# Precision_Arduino_Charlieplex.net
KiCad netlist of a schematic drawn in EAGLE
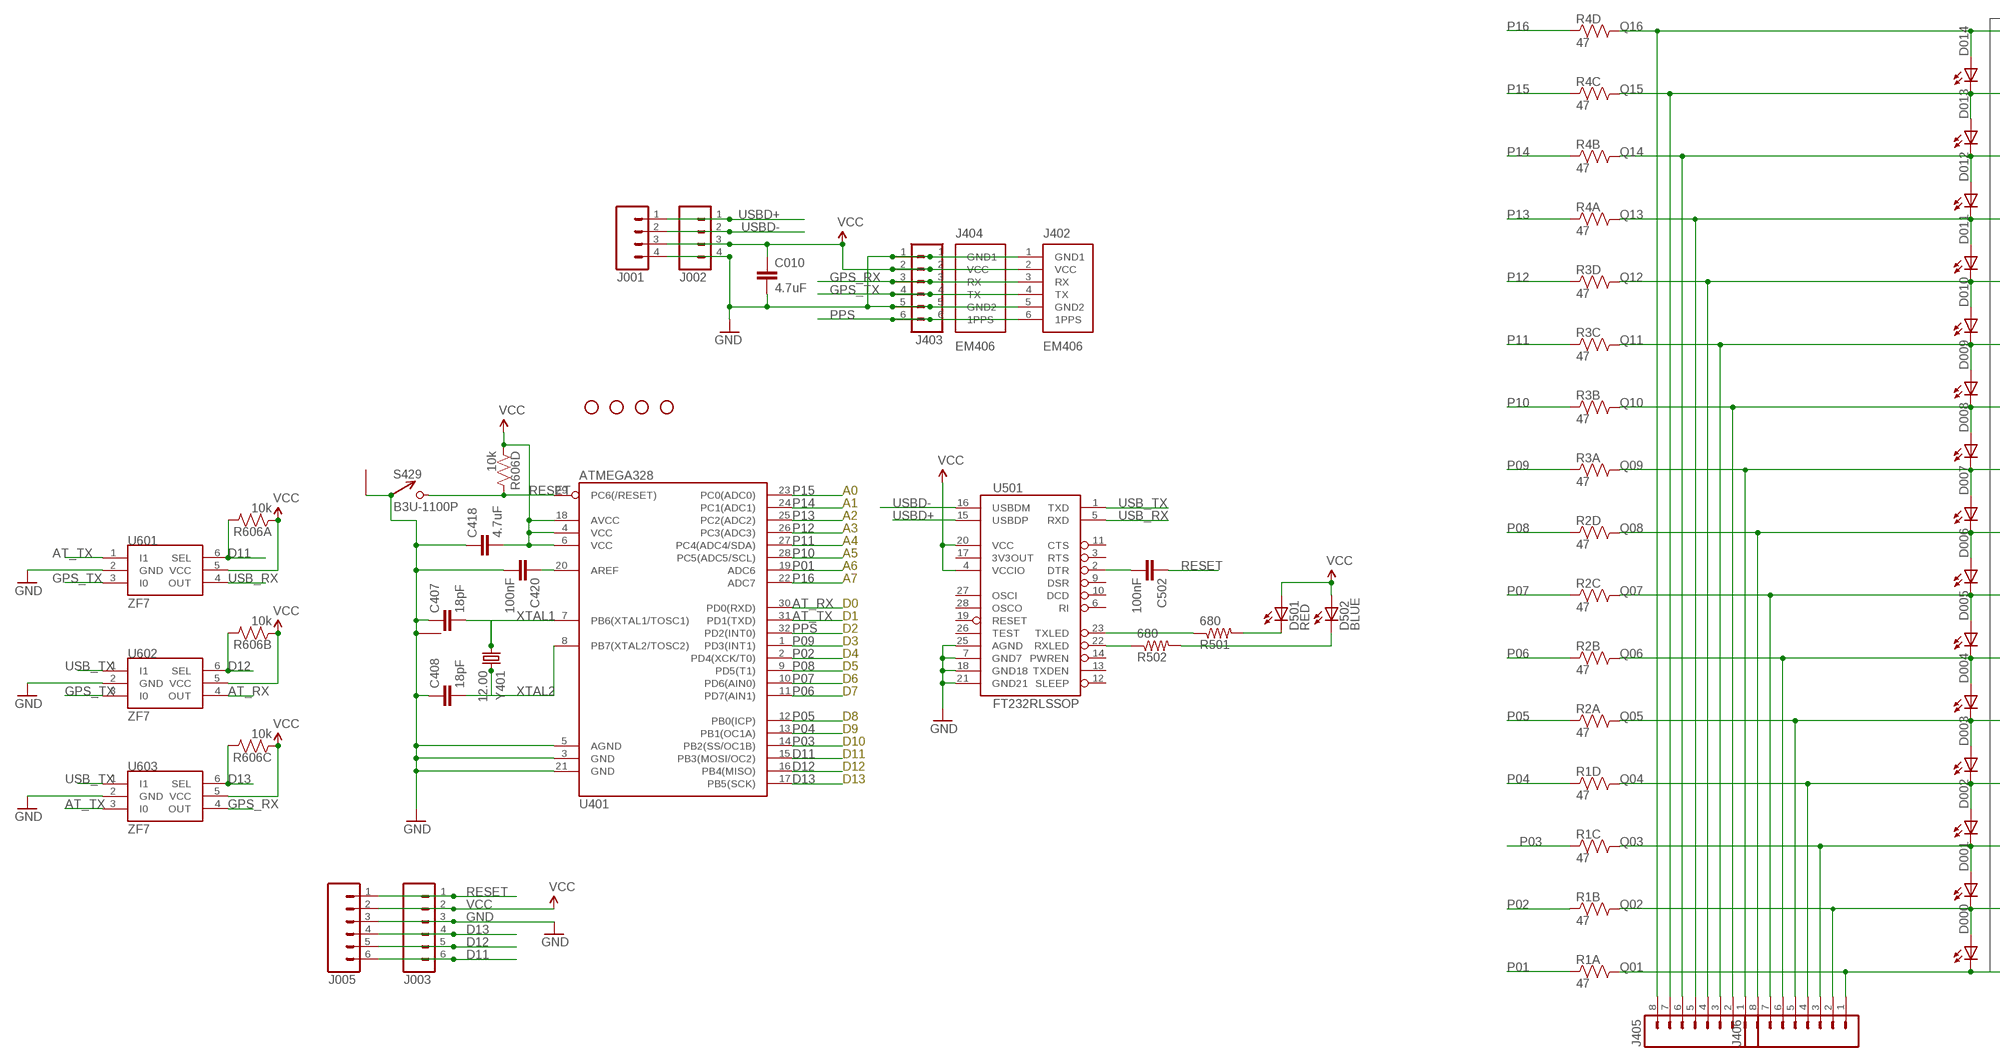
[diagram p0: schematic, sheet 1, part 1 of 2]
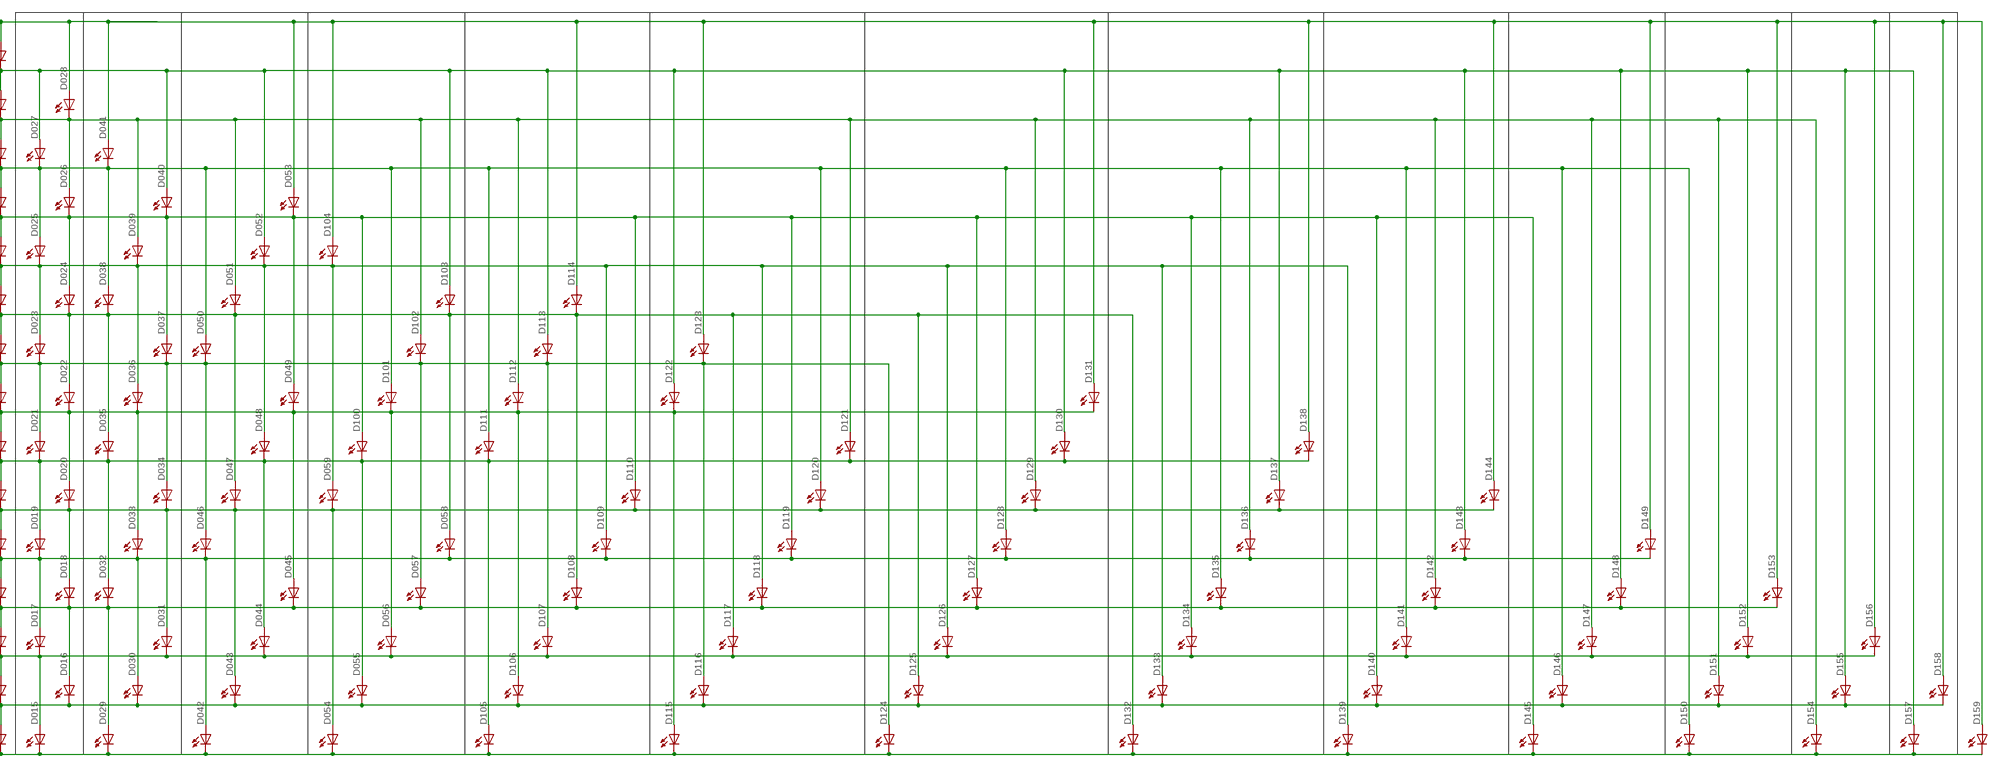
[diagram p1: schematic, sheet 1, part 2 of 2]

(export (version "E")
  (design (tool "Eeschema 10.0.6"))
  (components
    (comp (ref "C010")
      (value "4.7uF")
      (footprint "eagle-import:0603-CAP")
      (libsource (lib "eagle-import") (part "CAP0603-CAP"))
    )
    (comp (ref "C407")
      (value "18pF")
      (footprint "eagle-import:0603-CAP")
      (libsource (lib "eagle-import") (part "CAP0603-CAP"))
    )
    (comp (ref "C408")
      (value "18pF")
      (footprint "eagle-import:0603-CAP")
      (libsource (lib "eagle-import") (part "CAP0603-CAP"))
    )
    (comp (ref "C418")
      (value "4.7uF")
      (footprint "eagle-import:0603-CAP")
      (libsource (lib "eagle-import") (part "CAP0603-CAP"))
    )
    (comp (ref "C420")
      (value "100nF")
      (footprint "eagle-import:0603-CAP")
      (libsource (lib "eagle-import") (part "CAP0603-CAP"))
    )
    (comp (ref "C502")
      (value "100nF")
      (footprint "eagle-import:0603-CAP")
      (libsource (lib "eagle-import") (part "CAP0603-CAP"))
    )
    (comp (ref "D000")
      (value "HOUR")
      (footprint "eagle-import:LED-0603")
      (libsource (lib "eagle-import") (part "LED0603"))
    )
    (comp (ref "D001")
      (value "HOUR")
      (footprint "eagle-import:LED-0603")
      (libsource (lib "eagle-import") (part "LED0603"))
    )
    (comp (ref "D002")
      (value "HOUR")
      (footprint "eagle-import:LED-0603")
      (libsource (lib "eagle-import") (part "LED0603"))
    )
    (comp (ref "D003")
      (value "HOUR")
      (footprint "eagle-import:LED-0603")
      (libsource (lib "eagle-import") (part "LED0603"))
    )
    (comp (ref "D004")
      (value "HOUR")
      (footprint "eagle-import:LED-0603")
      (libsource (lib "eagle-import") (part "LED0603"))
    )
    (comp (ref "D005")
      (value "HOUR")
      (footprint "eagle-import:LED-0603")
      (libsource (lib "eagle-import") (part "LED0603"))
    )
    (comp (ref "D006")
      (value "HOUR")
      (footprint "eagle-import:LED-0603")
      (libsource (lib "eagle-import") (part "LED0603"))
    )
    (comp (ref "D007")
      (value "HOUR")
      (footprint "eagle-import:LED-0603")
      (libsource (lib "eagle-import") (part "LED0603"))
    )
    (comp (ref "D008")
      (value "HOUR")
      (footprint "eagle-import:LED-0603")
      (libsource (lib "eagle-import") (part "LED0603"))
    )
    (comp (ref "D009")
      (value "HOUR")
      (footprint "eagle-import:LED-0603")
      (libsource (lib "eagle-import") (part "LED0603"))
    )
    (comp (ref "D010")
      (value "HOUR")
      (footprint "eagle-import:LED-0603")
      (libsource (lib "eagle-import") (part "LED0603"))
    )
    (comp (ref "D011")
      (value "HOUR")
      (footprint "eagle-import:LED-0603")
      (libsource (lib "eagle-import") (part "LED0603"))
    )
    (comp (ref "D012")
      (value "HOUR")
      (footprint "eagle-import:LED-0603")
      (libsource (lib "eagle-import") (part "LED0603"))
    )
    (comp (ref "D013")
      (value "HOUR")
      (footprint "eagle-import:LED-0603")
      (libsource (lib "eagle-import") (part "LED0603"))
    )
    (comp (ref "D014")
      (value "HOUR")
      (footprint "eagle-import:LED-0603")
      (libsource (lib "eagle-import") (part "LED0603"))
    )
    (comp (ref "D015")
      (value "HOUR")
      (footprint "eagle-import:LED-0603")
      (libsource (lib "eagle-import") (part "LED0603"))
    )
    (comp (ref "D016")
      (value "HOUR")
      (footprint "eagle-import:LED-0603")
      (libsource (lib "eagle-import") (part "LED0603"))
    )
    (comp (ref "D017")
      (value "HOUR")
      (footprint "eagle-import:LED-0603")
      (libsource (lib "eagle-import") (part "LED0603"))
    )
    (comp (ref "D018")
      (value "HOUR")
      (footprint "eagle-import:LED-0603")
      (libsource (lib "eagle-import") (part "LED0603"))
    )
    (comp (ref "D019")
      (value "HOUR")
      (footprint "eagle-import:LED-0603")
      (libsource (lib "eagle-import") (part "LED0603"))
    )
    (comp (ref "D020")
      (value "HOUR")
      (footprint "eagle-import:LED-0603")
      (libsource (lib "eagle-import") (part "LED0603"))
    )
    (comp (ref "D021")
      (value "HOUR")
      (footprint "eagle-import:LED-0603")
      (libsource (lib "eagle-import") (part "LED0603"))
    )
    (comp (ref "D022")
      (value "HOUR")
      (footprint "eagle-import:LED-0603")
      (libsource (lib "eagle-import") (part "LED0603"))
    )
    (comp (ref "D023")
      (value "HOUR")
      (footprint "eagle-import:LED-0603")
      (libsource (lib "eagle-import") (part "LED0603"))
    )
    (comp (ref "D024")
      (value "HOUR")
      (footprint "eagle-import:LED-0603")
      (libsource (lib "eagle-import") (part "LED0603"))
    )
    (comp (ref "D025")
      (value "HOUR")
      (footprint "eagle-import:LED-0603")
      (libsource (lib "eagle-import") (part "LED0603"))
    )
    (comp (ref "D026")
      (value "HOUR")
      (footprint "eagle-import:LED-0603")
      (libsource (lib "eagle-import") (part "LED0603"))
    )
    (comp (ref "D027")
      (value "HOUR")
      (footprint "eagle-import:LED-0603")
      (libsource (lib "eagle-import") (part "LED0603"))
    )
    (comp (ref "D028")
      (value "HOUR")
      (footprint "eagle-import:LED-0603")
      (libsource (lib "eagle-import") (part "LED0603"))
    )
    (comp (ref "D029")
      (value "HOUR")
      (footprint "eagle-import:LED-0603")
      (libsource (lib "eagle-import") (part "LED0603"))
    )
    (comp (ref "D030")
      (value "HOUR")
      (footprint "eagle-import:LED-0603")
      (libsource (lib "eagle-import") (part "LED0603"))
    )
    (comp (ref "D031")
      (value "HOUR")
      (footprint "eagle-import:LED-0603")
      (libsource (lib "eagle-import") (part "LED0603"))
    )
    (comp (ref "D032")
      (value "HOUR")
      (footprint "eagle-import:LED-0603")
      (libsource (lib "eagle-import") (part "LED0603"))
    )
    (comp (ref "D033")
      (value "HOUR")
      (footprint "eagle-import:LED-0603")
      (libsource (lib "eagle-import") (part "LED0603"))
    )
    (comp (ref "D034")
      (value "HOUR")
      (footprint "eagle-import:LED-0603")
      (libsource (lib "eagle-import") (part "LED0603"))
    )
    (comp (ref "D035")
      (value "HOUR")
      (footprint "eagle-import:LED-0603")
      (libsource (lib "eagle-import") (part "LED0603"))
    )
    (comp (ref "D036")
      (value "HOUR")
      (footprint "eagle-import:LED-0603")
      (libsource (lib "eagle-import") (part "LED0603"))
    )
    (comp (ref "D037")
      (value "HOUR")
      (footprint "eagle-import:LED-0603")
      (libsource (lib "eagle-import") (part "LED0603"))
    )
    (comp (ref "D038")
      (value "HOUR")
      (footprint "eagle-import:LED-0603")
      (libsource (lib "eagle-import") (part "LED0603"))
    )
    (comp (ref "D039")
      (value "HOUR")
      (footprint "eagle-import:LED-0603")
      (libsource (lib "eagle-import") (part "LED0603"))
    )
    (comp (ref "D040")
      (value "HOUR")
      (footprint "eagle-import:LED-0603")
      (libsource (lib "eagle-import") (part "LED0603"))
    )
    (comp (ref "D041")
      (value "HOUR")
      (footprint "eagle-import:LED-0603")
      (libsource (lib "eagle-import") (part "LED0603"))
    )
    (comp (ref "D042")
      (value "HOUR")
      (footprint "eagle-import:LED-0603")
      (libsource (lib "eagle-import") (part "LED0603"))
    )
    (comp (ref "D043")
      (value "HOUR")
      (footprint "eagle-import:LED-0603")
      (libsource (lib "eagle-import") (part "LED0603"))
    )
    (comp (ref "D044")
      (value "HOUR")
      (footprint "eagle-import:LED-0603")
      (libsource (lib "eagle-import") (part "LED0603"))
    )
    (comp (ref "D045")
      (value "HOUR")
      (footprint "eagle-import:LED-0603")
      (libsource (lib "eagle-import") (part "LED0603"))
    )
    (comp (ref "D046")
      (value "HOUR")
      (footprint "eagle-import:LED-0603")
      (libsource (lib "eagle-import") (part "LED0603"))
    )
    (comp (ref "D047")
      (value "HOUR")
      (footprint "eagle-import:LED-0603")
      (libsource (lib "eagle-import") (part "LED0603"))
    )
    (comp (ref "D048")
      (value "HOUR")
      (footprint "eagle-import:LED-0603")
      (libsource (lib "eagle-import") (part "LED0603"))
    )
    (comp (ref "D049")
      (value "HOUR")
      (footprint "eagle-import:LED-0603")
      (libsource (lib "eagle-import") (part "LED0603"))
    )
    (comp (ref "D050")
      (value "HOUR")
      (footprint "eagle-import:LED-0603")
      (libsource (lib "eagle-import") (part "LED0603"))
    )
    (comp (ref "D051")
      (value "HOUR")
      (footprint "eagle-import:LED-0603")
      (libsource (lib "eagle-import") (part "LED0603"))
    )
    (comp (ref "D052")
      (value "HOUR")
      (footprint "eagle-import:LED-0603")
      (libsource (lib "eagle-import") (part "LED0603"))
    )
    (comp (ref "D053")
      (value "HOUR")
      (footprint "eagle-import:LED-0603")
      (libsource (lib "eagle-import") (part "LED0603"))
    )
    (comp (ref "D054")
      (value "HOUR")
      (footprint "eagle-import:LED-0603")
      (libsource (lib "eagle-import") (part "LED0603"))
    )
    (comp (ref "D055")
      (value "HOUR")
      (footprint "eagle-import:LED-0603")
      (libsource (lib "eagle-import") (part "LED0603"))
    )
    (comp (ref "D056")
      (value "HOUR")
      (footprint "eagle-import:LED-0603")
      (libsource (lib "eagle-import") (part "LED0603"))
    )
    (comp (ref "D057")
      (value "HOUR")
      (footprint "eagle-import:LED-0603")
      (libsource (lib "eagle-import") (part "LED0603"))
    )
    (comp (ref "D058")
      (value "HOUR")
      (footprint "eagle-import:LED-0603")
      (libsource (lib "eagle-import") (part "LED0603"))
    )
    (comp (ref "D059")
      (value "HOUR")
      (footprint "eagle-import:LED-0603")
      (libsource (lib "eagle-import") (part "LED0603"))
    )
    (comp (ref "D100")
      (value "HOUR")
      (footprint "eagle-import:LED-0603")
      (libsource (lib "eagle-import") (part "LED0603"))
    )
    (comp (ref "D101")
      (value "HOUR")
      (footprint "eagle-import:LED-0603")
      (libsource (lib "eagle-import") (part "LED0603"))
    )
    (comp (ref "D102")
      (value "HOUR")
      (footprint "eagle-import:LED-0603")
      (libsource (lib "eagle-import") (part "LED0603"))
    )
    (comp (ref "D103")
      (value "HOUR")
      (footprint "eagle-import:LED-0603")
      (libsource (lib "eagle-import") (part "LED0603"))
    )
    (comp (ref "D104")
      (value "HOUR")
      (footprint "eagle-import:LED-0603")
      (libsource (lib "eagle-import") (part "LED0603"))
    )
    (comp (ref "D105")
      (value "HOUR")
      (footprint "eagle-import:LED-0603")
      (libsource (lib "eagle-import") (part "LED0603"))
    )
    (comp (ref "D106")
      (value "HOUR")
      (footprint "eagle-import:LED-0603")
      (libsource (lib "eagle-import") (part "LED0603"))
    )
    (comp (ref "D107")
      (value "HOUR")
      (footprint "eagle-import:LED-0603")
      (libsource (lib "eagle-import") (part "LED0603"))
    )
    (comp (ref "D108")
      (value "HOUR")
      (footprint "eagle-import:LED-0603")
      (libsource (lib "eagle-import") (part "LED0603"))
    )
    (comp (ref "D109")
      (value "HOUR")
      (footprint "eagle-import:LED-0603")
      (libsource (lib "eagle-import") (part "LED0603"))
    )
    (comp (ref "D110")
      (value "HOUR")
      (footprint "eagle-import:LED-0603")
      (libsource (lib "eagle-import") (part "LED0603"))
    )
    (comp (ref "D111")
      (value "HOUR")
      (footprint "eagle-import:LED-0603")
      (libsource (lib "eagle-import") (part "LED0603"))
    )
    (comp (ref "D112")
      (value "HOUR")
      (footprint "eagle-import:LED-0603")
      (libsource (lib "eagle-import") (part "LED0603"))
    )
    (comp (ref "D113")
      (value "HOUR")
      (footprint "eagle-import:LED-0603")
      (libsource (lib "eagle-import") (part "LED0603"))
    )
    (comp (ref "D114")
      (value "HOUR")
      (footprint "eagle-import:LED-0603")
      (libsource (lib "eagle-import") (part "LED0603"))
    )
    (comp (ref "D115")
      (value "HOUR")
      (footprint "eagle-import:LED-0603")
      (libsource (lib "eagle-import") (part "LED0603"))
    )
    (comp (ref "D116")
      (value "HOUR")
      (footprint "eagle-import:LED-0603")
      (libsource (lib "eagle-import") (part "LED0603"))
    )
    (comp (ref "D117")
      (value "HOUR")
      (footprint "eagle-import:LED-0603")
      (libsource (lib "eagle-import") (part "LED0603"))
    )
    (comp (ref "D118")
      (value "HOUR")
      (footprint "eagle-import:LED-0603")
      (libsource (lib "eagle-import") (part "LED0603"))
    )
    (comp (ref "D119")
      (value "HOUR")
      (footprint "eagle-import:LED-0603")
      (libsource (lib "eagle-import") (part "LED0603"))
    )
    (comp (ref "D120")
      (value "HOUR")
      (footprint "eagle-import:LED-0603")
      (libsource (lib "eagle-import") (part "LED0603"))
    )
    (comp (ref "D121")
      (value "HOUR")
      (footprint "eagle-import:LED-0603")
      (libsource (lib "eagle-import") (part "LED0603"))
    )
    (comp (ref "D122")
      (value "HOUR")
      (footprint "eagle-import:LED-0603")
      (libsource (lib "eagle-import") (part "LED0603"))
    )
    (comp (ref "D123")
      (value "HOUR")
      (footprint "eagle-import:LED-0603")
      (libsource (lib "eagle-import") (part "LED0603"))
    )
    (comp (ref "D124")
      (value "HOUR")
      (footprint "eagle-import:LED-0603")
      (libsource (lib "eagle-import") (part "LED0603"))
    )
    (comp (ref "D125")
      (value "HOUR")
      (footprint "eagle-import:LED-0603")
      (libsource (lib "eagle-import") (part "LED0603"))
    )
    (comp (ref "D126")
      (value "HOUR")
      (footprint "eagle-import:LED-0603")
      (libsource (lib "eagle-import") (part "LED0603"))
    )
    (comp (ref "D127")
      (value "HOUR")
      (footprint "eagle-import:LED-0603")
      (libsource (lib "eagle-import") (part "LED0603"))
    )
    (comp (ref "D128")
      (value "HOUR")
      (footprint "eagle-import:LED-0603")
      (libsource (lib "eagle-import") (part "LED0603"))
    )
    (comp (ref "D129")
      (value "HOUR")
      (footprint "eagle-import:LED-0603")
      (libsource (lib "eagle-import") (part "LED0603"))
    )
    (comp (ref "D130")
      (value "HOUR")
      (footprint "eagle-import:LED-0603")
      (libsource (lib "eagle-import") (part "LED0603"))
    )
    (comp (ref "D131")
      (value "HOUR")
      (footprint "eagle-import:LED-0603")
      (libsource (lib "eagle-import") (part "LED0603"))
    )
    (comp (ref "D132")
      (value "HOUR")
      (footprint "eagle-import:LED-0603")
      (libsource (lib "eagle-import") (part "LED0603"))
    )
    (comp (ref "D133")
      (value "HOUR")
      (footprint "eagle-import:LED-0603")
      (libsource (lib "eagle-import") (part "LED0603"))
    )
    (comp (ref "D134")
      (value "HOUR")
      (footprint "eagle-import:LED-0603")
      (libsource (lib "eagle-import") (part "LED0603"))
    )
    (comp (ref "D135")
      (value "HOUR")
      (footprint "eagle-import:LED-0603")
      (libsource (lib "eagle-import") (part "LED0603"))
    )
    (comp (ref "D136")
      (value "HOUR")
      (footprint "eagle-import:LED-0603")
      (libsource (lib "eagle-import") (part "LED0603"))
    )
    (comp (ref "D137")
      (value "HOUR")
      (footprint "eagle-import:LED-0603")
      (libsource (lib "eagle-import") (part "LED0603"))
    )
    (comp (ref "D138")
      (value "HOUR")
      (footprint "eagle-import:LED-0603")
      (libsource (lib "eagle-import") (part "LED0603"))
    )
    (comp (ref "D139")
      (value "HOUR")
      (footprint "eagle-import:LED-0603")
      (libsource (lib "eagle-import") (part "LED0603"))
    )
    (comp (ref "D140")
      (value "HOUR")
      (footprint "eagle-import:LED-0603")
      (libsource (lib "eagle-import") (part "LED0603"))
    )
    (comp (ref "D141")
      (value "HOUR")
      (footprint "eagle-import:LED-0603")
      (libsource (lib "eagle-import") (part "LED0603"))
    )
    (comp (ref "D142")
      (value "HOUR")
      (footprint "eagle-import:LED-0603")
      (libsource (lib "eagle-import") (part "LED0603"))
    )
    (comp (ref "D143")
      (value "HOUR")
      (footprint "eagle-import:LED-0603")
      (libsource (lib "eagle-import") (part "LED0603"))
    )
    (comp (ref "D144")
      (value "HOUR")
      (footprint "eagle-import:LED-0603")
      (libsource (lib "eagle-import") (part "LED0603"))
    )
    (comp (ref "D145")
      (value "HOUR")
      (footprint "eagle-import:LED-0603")
      (libsource (lib "eagle-import") (part "LED0603"))
    )
    (comp (ref "D146")
      (value "HOUR")
      (footprint "eagle-import:LED-0603")
      (libsource (lib "eagle-import") (part "LED0603"))
    )
    (comp (ref "D147")
      (value "HOUR")
      (footprint "eagle-import:LED-0603")
      (libsource (lib "eagle-import") (part "LED0603"))
    )
    (comp (ref "D148")
      (value "HOUR")
      (footprint "eagle-import:LED-0603")
      (libsource (lib "eagle-import") (part "LED0603"))
    )
    (comp (ref "D149")
      (value "HOUR")
      (footprint "eagle-import:LED-0603")
      (libsource (lib "eagle-import") (part "LED0603"))
    )
    (comp (ref "D150")
      (value "HOUR")
      (footprint "eagle-import:LED-0603")
      (libsource (lib "eagle-import") (part "LED0603"))
    )
    (comp (ref "D151")
      (value "HOUR")
      (footprint "eagle-import:LED-0603")
      (libsource (lib "eagle-import") (part "LED0603"))
    )
    (comp (ref "D152")
      (value "HOUR")
      (footprint "eagle-import:LED-0603")
      (libsource (lib "eagle-import") (part "LED0603"))
    )
    (comp (ref "D153")
      (value "HOUR")
      (footprint "eagle-import:LED-0603")
      (libsource (lib "eagle-import") (part "LED0603"))
    )
    (comp (ref "D154")
      (value "HOUR")
      (footprint "eagle-import:LED-0603")
      (libsource (lib "eagle-import") (part "LED0603"))
    )
    (comp (ref "D155")
      (value "HOUR")
      (footprint "eagle-import:LED-0603")
      (libsource (lib "eagle-import") (part "LED0603"))
    )
    (comp (ref "D156")
      (value "HOUR")
      (footprint "eagle-import:LED-0603")
      (libsource (lib "eagle-import") (part "LED0603"))
    )
    (comp (ref "D157")
      (value "HOUR")
      (footprint "eagle-import:LED-0603")
      (libsource (lib "eagle-import") (part "LED0603"))
    )
    (comp (ref "D158")
      (value "HOUR")
      (footprint "eagle-import:LED-0603")
      (libsource (lib "eagle-import") (part "LED0603"))
    )
    (comp (ref "D159")
      (value "HOUR")
      (footprint "eagle-import:LED-0603")
      (libsource (lib "eagle-import") (part "LED0603"))
    )
    (comp (ref "D501")
      (value "RED")
      (footprint "eagle-import:LED-0603")
      (libsource (lib "eagle-import") (part "LED0603"))
    )
    (comp (ref "D502")
      (value "BLUE")
      (footprint "eagle-import:LED-0603")
      (libsource (lib "eagle-import") (part "LED0603"))
    )
    (comp (ref "J001")
      (value "M04PTH")
      (footprint "eagle-import:1X04")
      (libsource (lib "eagle-import") (part "M04PTH"))
    )
    (comp (ref "J002")
      (value "M04PTH")
      (footprint "eagle-import:1X04")
      (libsource (lib "eagle-import") (part "M04PTH"))
    )
    (comp (ref "J003")
      (value "M06SIP")
      (footprint "eagle-import:1X06")
      (libsource (lib "eagle-import") (part "M06SIP"))
    )
    (comp (ref "J005")
      (value "M06SIP")
      (footprint "eagle-import:1X06")
      (libsource (lib "eagle-import") (part "M06SIP"))
    )
    (comp (ref "J402")
      (value "EM406")
      (footprint "eagle-import:EM406")
      (libsource (lib "eagle-import") (part "EM406"))
    )
    (comp (ref "J403")
      (value "M06SIP")
      (footprint "eagle-import:1X06")
      (libsource (lib "eagle-import") (part "M06SIP"))
    )
    (comp (ref "J404")
      (value "EM406")
      (footprint "eagle-import:EM406")
      (libsource (lib "eagle-import") (part "EM406"))
    )
    (comp (ref "J405")
      (value "M081X08")
      (footprint "eagle-import:1X08")
      (libsource (lib "eagle-import") (part "M081X08"))
    )
    (comp (ref "J406")
      (value "M081X08")
      (footprint "eagle-import:1X08")
      (libsource (lib "eagle-import") (part "M081X08"))
    )
    (comp (ref "JP1")
      (value "STAND-OFF")
      (footprint "eagle-import:STAND-OFF")
      (libsource (lib "eagle-import") (part "STAND-OFF"))
    )
    (comp (ref "JP2")
      (value "STAND-OFF")
      (footprint "eagle-import:STAND-OFF")
      (libsource (lib "eagle-import") (part "STAND-OFF"))
    )
    (comp (ref "JP3")
      (value "STAND-OFF")
      (footprint "eagle-import:STAND-OFF")
      (libsource (lib "eagle-import") (part "STAND-OFF"))
    )
    (comp (ref "JP4")
      (value "STAND-OFF")
      (footprint "eagle-import:STAND-OFF")
      (libsource (lib "eagle-import") (part "STAND-OFF"))
    )
    (comp (ref "R1")
      (value "47")
      (footprint "eagle-import:CRA04")
      (libsource (lib "eagle-import") (part "RP404"))
    )
    (comp (ref "R2")
      (value "47")
      (footprint "eagle-import:CRA04")
      (libsource (lib "eagle-import") (part "RP404"))
    )
    (comp (ref "R3")
      (value "47")
      (footprint "eagle-import:CRA04")
      (libsource (lib "eagle-import") (part "RP404"))
    )
    (comp (ref "R4")
      (value "47")
      (footprint "eagle-import:CRA04")
      (libsource (lib "eagle-import") (part "RP404"))
    )
    (comp (ref "R501")
      (value "680")
      (footprint "eagle-import:0603-RES")
      (libsource (lib "eagle-import") (part "RESISTOR0603-RES"))
    )
    (comp (ref "R502")
      (value "680")
      (footprint "eagle-import:0603-RES")
      (libsource (lib "eagle-import") (part "RESISTOR0603-RES"))
    )
    (comp (ref "R606")
      (value "10k")
      (footprint "eagle-import:CRA04")
      (libsource (lib "eagle-import") (part "RP404"))
    )
    (comp (ref "S429")
      (value "B3U-1100P")
      (footprint "eagle-import:B3U-1100P")
      (libsource (lib "eagle-import") (part "B3U-1100P"))
    )
    (comp (ref "U401")
      (value "ATMEGA328")
      (footprint "eagle-import:TQFP32-08")
      (libsource (lib "eagle-import") (part "ATMEGA168"))
    )
    (comp (ref "U501")
      (value "FT232RLSSOP")
      (footprint "eagle-import:SSOP28DB")
      (libsource (lib "eagle-import") (part "FT232RLSSOP"))
    )
    (comp (ref "U601")
      (value "ZF7")
      (footprint "eagle-import:SC-70-6")
      (libsource (lib "eagle-import") (part "NC7SZ157"))
    )
    (comp (ref "U602")
      (value "ZF7")
      (footprint "eagle-import:SC-70-6")
      (libsource (lib "eagle-import") (part "NC7SZ157"))
    )
    (comp (ref "U603")
      (value "ZF7")
      (footprint "eagle-import:SC-70-6")
      (libsource (lib "eagle-import") (part "NC7SZ157"))
    )
    (comp (ref "Y401")
      (value "12.00")
      (footprint "eagle-import:CRYSTAL_SMD")
      (libsource (lib "eagle-import") (part "TSX-3225"))
    )
  )
  (nets
    (net (code "1") (name "/AT_RX") (class "Default")
      (node (ref "U401") (pin "30") (pinfunction "PD0(RXD)_30") (pintype "bidirectional"))
      (node (ref "U602") (pin "4") (pinfunction "OUT_4") (pintype "bidirectional"))
    )
    (net (code "2") (name "/AT_TX") (class "Default")
      (node (ref "U401") (pin "31") (pinfunction "PD1(TXD)_31") (pintype "bidirectional"))
      (node (ref "U601") (pin "1") (pinfunction "I1_1") (pintype "bidirectional"))
      (node (ref "U603") (pin "3") (pinfunction "I0_3") (pintype "bidirectional"))
    )
    (net (code "3") (name "/D11") (class "Default")
      (node (ref "J003") (pin "6") (pinfunction "6_6") (pintype "passive"))
      (node (ref "J005") (pin "6") (pinfunction "6_6") (pintype "passive"))
      (node (ref "R606") (pin "8") (pinfunction "2_8") (pintype "passive"))
      (node (ref "U401") (pin "15") (pinfunction "PB3(MOSI/OC2)_15") (pintype "bidirectional"))
      (node (ref "U601") (pin "6") (pinfunction "SEL_6") (pintype "bidirectional"))
    )
    (net (code "4") (name "/D12") (class "Default")
      (node (ref "J003") (pin "5") (pinfunction "5_5") (pintype "passive"))
      (node (ref "J005") (pin "5") (pinfunction "5_5") (pintype "passive"))
      (node (ref "R606") (pin "7") (pinfunction "2_7") (pintype "passive"))
      (node (ref "U401") (pin "16") (pinfunction "PB4(MISO)_16") (pintype "bidirectional"))
      (node (ref "U602") (pin "6") (pinfunction "SEL_6") (pintype "bidirectional"))
    )
    (net (code "5") (name "/D13") (class "Default")
      (node (ref "J003") (pin "4") (pinfunction "4_4") (pintype "passive"))
      (node (ref "J005") (pin "4") (pinfunction "4_4") (pintype "passive"))
      (node (ref "R606") (pin "6") (pinfunction "2_6") (pintype "passive"))
      (node (ref "U401") (pin "17") (pinfunction "PB5(SCK)_17") (pintype "bidirectional"))
      (node (ref "U603") (pin "6") (pinfunction "SEL_6") (pintype "bidirectional"))
    )
    (net (code "6") (name "/GPS_RX") (class "Default")
      (node (ref "J402") (pin "3") (pinfunction "RX_3") (pintype "bidirectional"))
      (node (ref "J403") (pin "3") (pinfunction "3_3") (pintype "passive"))
      (node (ref "J404") (pin "3") (pinfunction "RX_3") (pintype "bidirectional"))
      (node (ref "U603") (pin "4") (pinfunction "OUT_4") (pintype "bidirectional"))
    )
    (net (code "7") (name "/GPS_TX") (class "Default")
      (node (ref "J402") (pin "4") (pinfunction "TX_4") (pintype "bidirectional"))
      (node (ref "J403") (pin "4") (pinfunction "4_4") (pintype "passive"))
      (node (ref "J404") (pin "4") (pinfunction "TX_4") (pintype "bidirectional"))
      (node (ref "U601") (pin "3") (pinfunction "I0_3") (pintype "bidirectional"))
      (node (ref "U602") (pin "3") (pinfunction "I0_3") (pintype "bidirectional"))
    )
    (net (code "8") (name "/P01") (class "Default")
      (node (ref "R1") (pin "1") (pinfunction "1_1") (pintype "passive"))
      (node (ref "U401") (pin "19") (pinfunction "ADC6_19") (pintype "bidirectional"))
    )
    (net (code "9") (name "/P02") (class "Default")
      (node (ref "R1") (pin "2") (pinfunction "1_2") (pintype "passive"))
      (node (ref "U401") (pin "2") (pinfunction "PD4(XCK/T0)_2") (pintype "bidirectional"))
    )
    (net (code "10") (name "/P03") (class "Default")
      (node (ref "R1") (pin "3") (pinfunction "1_3") (pintype "passive"))
      (node (ref "U401") (pin "14") (pinfunction "PB2(SS/OC1B)_14") (pintype "bidirectional"))
    )
    (net (code "11") (name "/P04") (class "Default")
      (node (ref "R1") (pin "4") (pinfunction "1_4") (pintype "passive"))
      (node (ref "U401") (pin "13") (pinfunction "PB1(OC1A)_13") (pintype "bidirectional"))
    )
    (net (code "12") (name "/P05") (class "Default")
      (node (ref "R2") (pin "1") (pinfunction "1_1") (pintype "passive"))
      (node (ref "U401") (pin "12") (pinfunction "PB0(ICP)_12") (pintype "bidirectional"))
    )
    (net (code "13") (name "/P06") (class "Default")
      (node (ref "R2") (pin "2") (pinfunction "1_2") (pintype "passive"))
      (node (ref "U401") (pin "11") (pinfunction "PD7(AIN1)_11") (pintype "bidirectional"))
    )
    (net (code "14") (name "/P07") (class "Default")
      (node (ref "R2") (pin "3") (pinfunction "1_3") (pintype "passive"))
      (node (ref "U401") (pin "10") (pinfunction "PD6(AIN0)_10") (pintype "bidirectional"))
    )
    (net (code "15") (name "/P08") (class "Default")
      (node (ref "R2") (pin "4") (pinfunction "1_4") (pintype "passive"))
      (node (ref "U401") (pin "9") (pinfunction "PD5(T1)_9") (pintype "bidirectional"))
    )
    (net (code "16") (name "/P09") (class "Default")
      (node (ref "R3") (pin "1") (pinfunction "1_1") (pintype "passive"))
      (node (ref "U401") (pin "1") (pinfunction "PD3(INT1)_1") (pintype "bidirectional"))
    )
    (net (code "17") (name "/P10") (class "Default")
      (node (ref "R3") (pin "2") (pinfunction "1_2") (pintype "passive"))
      (node (ref "U401") (pin "28") (pinfunction "PC5(ADC5/SCL)_28") (pintype "bidirectional"))
    )
    (net (code "18") (name "/P11") (class "Default")
      (node (ref "R3") (pin "3") (pinfunction "1_3") (pintype "passive"))
      (node (ref "U401") (pin "27") (pinfunction "PC4(ADC4/SDA)_27") (pintype "bidirectional"))
    )
    (net (code "19") (name "/P12") (class "Default")
      (node (ref "R3") (pin "4") (pinfunction "1_4") (pintype "passive"))
      (node (ref "U401") (pin "26") (pinfunction "PC3(ADC3)_26") (pintype "bidirectional"))
    )
    (net (code "20") (name "/P13") (class "Default")
      (node (ref "R4") (pin "1") (pinfunction "1_1") (pintype "passive"))
      (node (ref "U401") (pin "25") (pinfunction "PC2(ADC2)_25") (pintype "bidirectional"))
    )
    (net (code "21") (name "/P14") (class "Default")
      (node (ref "R4") (pin "2") (pinfunction "1_2") (pintype "passive"))
      (node (ref "U401") (pin "24") (pinfunction "PC1(ADC1)_24") (pintype "bidirectional"))
    )
    (net (code "22") (name "/P15") (class "Default")
      (node (ref "R4") (pin "3") (pinfunction "1_3") (pintype "passive"))
      (node (ref "U401") (pin "23") (pinfunction "PC0(ADC0)_23") (pintype "bidirectional"))
    )
    (net (code "23") (name "/P16") (class "Default")
      (node (ref "R4") (pin "4") (pinfunction "1_4") (pintype "passive"))
      (node (ref "U401") (pin "22") (pinfunction "ADC7_22") (pintype "bidirectional"))
    )
    (net (code "24") (name "/PPS") (class "Default")
      (node (ref "J402") (pin "6") (pinfunction "1PPS_6") (pintype "bidirectional"))
      (node (ref "J403") (pin "6") (pinfunction "6_6") (pintype "passive"))
      (node (ref "J404") (pin "6") (pinfunction "1PPS_6") (pintype "bidirectional"))
      (node (ref "U401") (pin "32") (pinfunction "PD2(INT0)_32") (pintype "bidirectional"))
    )
    (net (code "25") (name "/Q01") (class "Default")
      (node (ref "D000") (pin "C") (pinfunction "C_C") (pintype "passive"))
      (node (ref "D015") (pin "C") (pinfunction "C_C") (pintype "passive"))
      (node (ref "D029") (pin "C") (pinfunction "C_C") (pintype "passive"))
      (node (ref "D042") (pin "C") (pinfunction "C_C") (pintype "passive"))
      (node (ref "D054") (pin "C") (pinfunction "C_C") (pintype "passive"))
      (node (ref "D105") (pin "C") (pinfunction "C_C") (pintype "passive"))
      (node (ref "D115") (pin "C") (pinfunction "C_C") (pintype "passive"))
      (node (ref "D124") (pin "C") (pinfunction "C_C") (pintype "passive"))
      (node (ref "D132") (pin "C") (pinfunction "C_C") (pintype "passive"))
      (node (ref "D139") (pin "C") (pinfunction "C_C") (pintype "passive"))
      (node (ref "D145") (pin "C") (pinfunction "C_C") (pintype "passive"))
      (node (ref "D150") (pin "C") (pinfunction "C_C") (pintype "passive"))
      (node (ref "D154") (pin "C") (pinfunction "C_C") (pintype "passive"))
      (node (ref "D157") (pin "C") (pinfunction "C_C") (pintype "passive"))
      (node (ref "D159") (pin "C") (pinfunction "C_C") (pintype "passive"))
      (node (ref "J406") (pin "1") (pinfunction "1_1") (pintype "passive"))
      (node (ref "R1") (pin "8") (pinfunction "2_8") (pintype "passive"))
    )
    (net (code "26") (name "/Q02") (class "Default")
      (node (ref "D000") (pin "A") (pinfunction "A_A") (pintype "passive"))
      (node (ref "D001") (pin "C") (pinfunction "C_C") (pintype "passive"))
      (node (ref "D016") (pin "C") (pinfunction "C_C") (pintype "passive"))
      (node (ref "D030") (pin "C") (pinfunction "C_C") (pintype "passive"))
      (node (ref "D043") (pin "C") (pinfunction "C_C") (pintype "passive"))
      (node (ref "D055") (pin "C") (pinfunction "C_C") (pintype "passive"))
      (node (ref "D106") (pin "C") (pinfunction "C_C") (pintype "passive"))
      (node (ref "D116") (pin "C") (pinfunction "C_C") (pintype "passive"))
      (node (ref "D125") (pin "C") (pinfunction "C_C") (pintype "passive"))
      (node (ref "D133") (pin "C") (pinfunction "C_C") (pintype "passive"))
      (node (ref "D140") (pin "C") (pinfunction "C_C") (pintype "passive"))
      (node (ref "D146") (pin "C") (pinfunction "C_C") (pintype "passive"))
      (node (ref "D151") (pin "C") (pinfunction "C_C") (pintype "passive"))
      (node (ref "D155") (pin "C") (pinfunction "C_C") (pintype "passive"))
      (node (ref "D158") (pin "C") (pinfunction "C_C") (pintype "passive"))
      (node (ref "J406") (pin "2") (pinfunction "2_2") (pintype "passive"))
      (node (ref "R1") (pin "7") (pinfunction "2_7") (pintype "passive"))
    )
    (net (code "27") (name "/Q03") (class "Default")
      (node (ref "D001") (pin "A") (pinfunction "A_A") (pintype "passive"))
      (node (ref "D002") (pin "C") (pinfunction "C_C") (pintype "passive"))
      (node (ref "D015") (pin "A") (pinfunction "A_A") (pintype "passive"))
      (node (ref "D017") (pin "C") (pinfunction "C_C") (pintype "passive"))
      (node (ref "D031") (pin "C") (pinfunction "C_C") (pintype "passive"))
      (node (ref "D044") (pin "C") (pinfunction "C_C") (pintype "passive"))
      (node (ref "D056") (pin "C") (pinfunction "C_C") (pintype "passive"))
      (node (ref "D107") (pin "C") (pinfunction "C_C") (pintype "passive"))
      (node (ref "D117") (pin "C") (pinfunction "C_C") (pintype "passive"))
      (node (ref "D126") (pin "C") (pinfunction "C_C") (pintype "passive"))
      (node (ref "D134") (pin "C") (pinfunction "C_C") (pintype "passive"))
      (node (ref "D141") (pin "C") (pinfunction "C_C") (pintype "passive"))
      (node (ref "D147") (pin "C") (pinfunction "C_C") (pintype "passive"))
      (node (ref "D152") (pin "C") (pinfunction "C_C") (pintype "passive"))
      (node (ref "D156") (pin "C") (pinfunction "C_C") (pintype "passive"))
      (node (ref "J406") (pin "3") (pinfunction "3_3") (pintype "passive"))
      (node (ref "R1") (pin "6") (pinfunction "2_6") (pintype "passive"))
    )
    (net (code "28") (name "/Q04") (class "Default")
      (node (ref "D002") (pin "A") (pinfunction "A_A") (pintype "passive"))
      (node (ref "D003") (pin "C") (pinfunction "C_C") (pintype "passive"))
      (node (ref "D016") (pin "A") (pinfunction "A_A") (pintype "passive"))
      (node (ref "D018") (pin "C") (pinfunction "C_C") (pintype "passive"))
      (node (ref "D029") (pin "A") (pinfunction "A_A") (pintype "passive"))
      (node (ref "D032") (pin "C") (pinfunction "C_C") (pintype "passive"))
      (node (ref "D045") (pin "C") (pinfunction "C_C") (pintype "passive"))
      (node (ref "D057") (pin "C") (pinfunction "C_C") (pintype "passive"))
      (node (ref "D108") (pin "C") (pinfunction "C_C") (pintype "passive"))
      (node (ref "D118") (pin "C") (pinfunction "C_C") (pintype "passive"))
      (node (ref "D127") (pin "C") (pinfunction "C_C") (pintype "passive"))
      (node (ref "D135") (pin "C") (pinfunction "C_C") (pintype "passive"))
      (node (ref "D142") (pin "C") (pinfunction "C_C") (pintype "passive"))
      (node (ref "D148") (pin "C") (pinfunction "C_C") (pintype "passive"))
      (node (ref "D153") (pin "C") (pinfunction "C_C") (pintype "passive"))
      (node (ref "J406") (pin "4") (pinfunction "4_4") (pintype "passive"))
      (node (ref "R1") (pin "5") (pinfunction "2_5") (pintype "passive"))
    )
    (net (code "29") (name "/Q05") (class "Default")
      (node (ref "D003") (pin "A") (pinfunction "A_A") (pintype "passive"))
      (node (ref "D004") (pin "C") (pinfunction "C_C") (pintype "passive"))
      (node (ref "D017") (pin "A") (pinfunction "A_A") (pintype "passive"))
      (node (ref "D019") (pin "C") (pinfunction "C_C") (pintype "passive"))
      (node (ref "D030") (pin "A") (pinfunction "A_A") (pintype "passive"))
      (node (ref "D033") (pin "C") (pinfunction "C_C") (pintype "passive"))
      (node (ref "D042") (pin "A") (pinfunction "A_A") (pintype "passive"))
      (node (ref "D046") (pin "C") (pinfunction "C_C") (pintype "passive"))
      (node (ref "D058") (pin "C") (pinfunction "C_C") (pintype "passive"))
      (node (ref "D109") (pin "C") (pinfunction "C_C") (pintype "passive"))
      (node (ref "D119") (pin "C") (pinfunction "C_C") (pintype "passive"))
      (node (ref "D128") (pin "C") (pinfunction "C_C") (pintype "passive"))
      (node (ref "D136") (pin "C") (pinfunction "C_C") (pintype "passive"))
      (node (ref "D143") (pin "C") (pinfunction "C_C") (pintype "passive"))
      (node (ref "D149") (pin "C") (pinfunction "C_C") (pintype "passive"))
      (node (ref "J406") (pin "5") (pinfunction "5_5") (pintype "passive"))
      (node (ref "R2") (pin "8") (pinfunction "2_8") (pintype "passive"))
    )
    (net (code "30") (name "/Q06") (class "Default")
      (node (ref "D004") (pin "A") (pinfunction "A_A") (pintype "passive"))
      (node (ref "D005") (pin "C") (pinfunction "C_C") (pintype "passive"))
      (node (ref "D018") (pin "A") (pinfunction "A_A") (pintype "passive"))
      (node (ref "D020") (pin "C") (pinfunction "C_C") (pintype "passive"))
      (node (ref "D031") (pin "A") (pinfunction "A_A") (pintype "passive"))
      (node (ref "D034") (pin "C") (pinfunction "C_C") (pintype "passive"))
      (node (ref "D043") (pin "A") (pinfunction "A_A") (pintype "passive"))
      (node (ref "D047") (pin "C") (pinfunction "C_C") (pintype "passive"))
      (node (ref "D054") (pin "A") (pinfunction "A_A") (pintype "passive"))
      (node (ref "D059") (pin "C") (pinfunction "C_C") (pintype "passive"))
      (node (ref "D110") (pin "C") (pinfunction "C_C") (pintype "passive"))
      (node (ref "D120") (pin "C") (pinfunction "C_C") (pintype "passive"))
      (node (ref "D129") (pin "C") (pinfunction "C_C") (pintype "passive"))
      (node (ref "D137") (pin "C") (pinfunction "C_C") (pintype "passive"))
      (node (ref "D144") (pin "C") (pinfunction "C_C") (pintype "passive"))
      (node (ref "J406") (pin "6") (pinfunction "6_6") (pintype "passive"))
      (node (ref "R2") (pin "7") (pinfunction "2_7") (pintype "passive"))
    )
    (net (code "31") (name "/Q07") (class "Default")
      (node (ref "D005") (pin "A") (pinfunction "A_A") (pintype "passive"))
      (node (ref "D006") (pin "C") (pinfunction "C_C") (pintype "passive"))
      (node (ref "D019") (pin "A") (pinfunction "A_A") (pintype "passive"))
      (node (ref "D021") (pin "C") (pinfunction "C_C") (pintype "passive"))
      (node (ref "D032") (pin "A") (pinfunction "A_A") (pintype "passive"))
      (node (ref "D035") (pin "C") (pinfunction "C_C") (pintype "passive"))
      (node (ref "D044") (pin "A") (pinfunction "A_A") (pintype "passive"))
      (node (ref "D048") (pin "C") (pinfunction "C_C") (pintype "passive"))
      (node (ref "D055") (pin "A") (pinfunction "A_A") (pintype "passive"))
      (node (ref "D100") (pin "C") (pinfunction "C_C") (pintype "passive"))
      (node (ref "D105") (pin "A") (pinfunction "A_A") (pintype "passive"))
      (node (ref "D111") (pin "C") (pinfunction "C_C") (pintype "passive"))
      (node (ref "D121") (pin "C") (pinfunction "C_C") (pintype "passive"))
      (node (ref "D130") (pin "C") (pinfunction "C_C") (pintype "passive"))
      (node (ref "D138") (pin "C") (pinfunction "C_C") (pintype "passive"))
      (node (ref "J406") (pin "7") (pinfunction "7_7") (pintype "passive"))
      (node (ref "R2") (pin "6") (pinfunction "2_6") (pintype "passive"))
    )
    (net (code "32") (name "/Q08") (class "Default")
      (node (ref "D006") (pin "A") (pinfunction "A_A") (pintype "passive"))
      (node (ref "D007") (pin "C") (pinfunction "C_C") (pintype "passive"))
      (node (ref "D020") (pin "A") (pinfunction "A_A") (pintype "passive"))
      (node (ref "D022") (pin "C") (pinfunction "C_C") (pintype "passive"))
      (node (ref "D033") (pin "A") (pinfunction "A_A") (pintype "passive"))
      (node (ref "D036") (pin "C") (pinfunction "C_C") (pintype "passive"))
      (node (ref "D045") (pin "A") (pinfunction "A_A") (pintype "passive"))
      (node (ref "D049") (pin "C") (pinfunction "C_C") (pintype "passive"))
      (node (ref "D056") (pin "A") (pinfunction "A_A") (pintype "passive"))
      (node (ref "D101") (pin "C") (pinfunction "C_C") (pintype "passive"))
      (node (ref "D106") (pin "A") (pinfunction "A_A") (pintype "passive"))
      (node (ref "D112") (pin "C") (pinfunction "C_C") (pintype "passive"))
      (node (ref "D115") (pin "A") (pinfunction "A_A") (pintype "passive"))
      (node (ref "D122") (pin "C") (pinfunction "C_C") (pintype "passive"))
      (node (ref "D131") (pin "C") (pinfunction "C_C") (pintype "passive"))
      (node (ref "J406") (pin "8") (pinfunction "8_8") (pintype "passive"))
      (node (ref "R2") (pin "5") (pinfunction "2_5") (pintype "passive"))
    )
    (net (code "33") (name "/Q09") (class "Default")
      (node (ref "D007") (pin "A") (pinfunction "A_A") (pintype "passive"))
      (node (ref "D008") (pin "C") (pinfunction "C_C") (pintype "passive"))
      (node (ref "D021") (pin "A") (pinfunction "A_A") (pintype "passive"))
      (node (ref "D023") (pin "C") (pinfunction "C_C") (pintype "passive"))
      (node (ref "D034") (pin "A") (pinfunction "A_A") (pintype "passive"))
      (node (ref "D037") (pin "C") (pinfunction "C_C") (pintype "passive"))
      (node (ref "D046") (pin "A") (pinfunction "A_A") (pintype "passive"))
      (node (ref "D050") (pin "C") (pinfunction "C_C") (pintype "passive"))
      (node (ref "D057") (pin "A") (pinfunction "A_A") (pintype "passive"))
      (node (ref "D102") (pin "C") (pinfunction "C_C") (pintype "passive"))
      (node (ref "D107") (pin "A") (pinfunction "A_A") (pintype "passive"))
      (node (ref "D113") (pin "C") (pinfunction "C_C") (pintype "passive"))
      (node (ref "D116") (pin "A") (pinfunction "A_A") (pintype "passive"))
      (node (ref "D123") (pin "C") (pinfunction "C_C") (pintype "passive"))
      (node (ref "D124") (pin "A") (pinfunction "A_A") (pintype "passive"))
      (node (ref "J405") (pin "1") (pinfunction "1_1") (pintype "passive"))
      (node (ref "R3") (pin "8") (pinfunction "2_8") (pintype "passive"))
    )
    (net (code "34") (name "/Q10") (class "Default")
      (node (ref "D008") (pin "A") (pinfunction "A_A") (pintype "passive"))
      (node (ref "D009") (pin "C") (pinfunction "C_C") (pintype "passive"))
      (node (ref "D022") (pin "A") (pinfunction "A_A") (pintype "passive"))
      (node (ref "D024") (pin "C") (pinfunction "C_C") (pintype "passive"))
      (node (ref "D035") (pin "A") (pinfunction "A_A") (pintype "passive"))
      (node (ref "D038") (pin "C") (pinfunction "C_C") (pintype "passive"))
      (node (ref "D047") (pin "A") (pinfunction "A_A") (pintype "passive"))
      (node (ref "D051") (pin "C") (pinfunction "C_C") (pintype "passive"))
      (node (ref "D058") (pin "A") (pinfunction "A_A") (pintype "passive"))
      (node (ref "D103") (pin "C") (pinfunction "C_C") (pintype "passive"))
      (node (ref "D108") (pin "A") (pinfunction "A_A") (pintype "passive"))
      (node (ref "D114") (pin "C") (pinfunction "C_C") (pintype "passive"))
      (node (ref "D117") (pin "A") (pinfunction "A_A") (pintype "passive"))
      (node (ref "D125") (pin "A") (pinfunction "A_A") (pintype "passive"))
      (node (ref "D132") (pin "A") (pinfunction "A_A") (pintype "passive"))
      (node (ref "J405") (pin "2") (pinfunction "2_2") (pintype "passive"))
      (node (ref "R3") (pin "7") (pinfunction "2_7") (pintype "passive"))
    )
    (net (code "35") (name "/Q11") (class "Default")
      (node (ref "D009") (pin "A") (pinfunction "A_A") (pintype "passive"))
      (node (ref "D010") (pin "C") (pinfunction "C_C") (pintype "passive"))
      (node (ref "D023") (pin "A") (pinfunction "A_A") (pintype "passive"))
      (node (ref "D025") (pin "C") (pinfunction "C_C") (pintype "passive"))
      (node (ref "D036") (pin "A") (pinfunction "A_A") (pintype "passive"))
      (node (ref "D039") (pin "C") (pinfunction "C_C") (pintype "passive"))
      (node (ref "D048") (pin "A") (pinfunction "A_A") (pintype "passive"))
      (node (ref "D052") (pin "C") (pinfunction "C_C") (pintype "passive"))
      (node (ref "D059") (pin "A") (pinfunction "A_A") (pintype "passive"))
      (node (ref "D104") (pin "C") (pinfunction "C_C") (pintype "passive"))
      (node (ref "D109") (pin "A") (pinfunction "A_A") (pintype "passive"))
      (node (ref "D118") (pin "A") (pinfunction "A_A") (pintype "passive"))
      (node (ref "D126") (pin "A") (pinfunction "A_A") (pintype "passive"))
      (node (ref "D133") (pin "A") (pinfunction "A_A") (pintype "passive"))
      (node (ref "D139") (pin "A") (pinfunction "A_A") (pintype "passive"))
      (node (ref "J405") (pin "3") (pinfunction "3_3") (pintype "passive"))
      (node (ref "R3") (pin "6") (pinfunction "2_6") (pintype "passive"))
    )
    (net (code "36") (name "/Q12") (class "Default")
      (node (ref "D010") (pin "A") (pinfunction "A_A") (pintype "passive"))
      (node (ref "D011") (pin "C") (pinfunction "C_C") (pintype "passive"))
      (node (ref "D024") (pin "A") (pinfunction "A_A") (pintype "passive"))
      (node (ref "D026") (pin "C") (pinfunction "C_C") (pintype "passive"))
      (node (ref "D037") (pin "A") (pinfunction "A_A") (pintype "passive"))
      (node (ref "D040") (pin "C") (pinfunction "C_C") (pintype "passive"))
      (node (ref "D049") (pin "A") (pinfunction "A_A") (pintype "passive"))
      (node (ref "D053") (pin "C") (pinfunction "C_C") (pintype "passive"))
      (node (ref "D100") (pin "A") (pinfunction "A_A") (pintype "passive"))
      (node (ref "D110") (pin "A") (pinfunction "A_A") (pintype "passive"))
      (node (ref "D119") (pin "A") (pinfunction "A_A") (pintype "passive"))
      (node (ref "D127") (pin "A") (pinfunction "A_A") (pintype "passive"))
      (node (ref "D134") (pin "A") (pinfunction "A_A") (pintype "passive"))
      (node (ref "D140") (pin "A") (pinfunction "A_A") (pintype "passive"))
      (node (ref "D145") (pin "A") (pinfunction "A_A") (pintype "passive"))
      (node (ref "J405") (pin "4") (pinfunction "4_4") (pintype "passive"))
      (node (ref "R3") (pin "5") (pinfunction "2_5") (pintype "passive"))
    )
    (net (code "37") (name "/Q13") (class "Default")
      (node (ref "D011") (pin "A") (pinfunction "A_A") (pintype "passive"))
      (node (ref "D012") (pin "C") (pinfunction "C_C") (pintype "passive"))
      (node (ref "D025") (pin "A") (pinfunction "A_A") (pintype "passive"))
      (node (ref "D027") (pin "C") (pinfunction "C_C") (pintype "passive"))
      (node (ref "D038") (pin "A") (pinfunction "A_A") (pintype "passive"))
      (node (ref "D041") (pin "C") (pinfunction "C_C") (pintype "passive"))
      (node (ref "D050") (pin "A") (pinfunction "A_A") (pintype "passive"))
      (node (ref "D101") (pin "A") (pinfunction "A_A") (pintype "passive"))
      (node (ref "D111") (pin "A") (pinfunction "A_A") (pintype "passive"))
      (node (ref "D120") (pin "A") (pinfunction "A_A") (pintype "passive"))
      (node (ref "D128") (pin "A") (pinfunction "A_A") (pintype "passive"))
      (node (ref "D135") (pin "A") (pinfunction "A_A") (pintype "passive"))
      (node (ref "D141") (pin "A") (pinfunction "A_A") (pintype "passive"))
      (node (ref "D146") (pin "A") (pinfunction "A_A") (pintype "passive"))
      (node (ref "D150") (pin "A") (pinfunction "A_A") (pintype "passive"))
      (node (ref "J405") (pin "5") (pinfunction "5_5") (pintype "passive"))
      (node (ref "R4") (pin "8") (pinfunction "2_8") (pintype "passive"))
    )
    (net (code "38") (name "/Q14") (class "Default")
      (node (ref "D012") (pin "A") (pinfunction "A_A") (pintype "passive"))
      (node (ref "D013") (pin "C") (pinfunction "C_C") (pintype "passive"))
      (node (ref "D026") (pin "A") (pinfunction "A_A") (pintype "passive"))
      (node (ref "D028") (pin "C") (pinfunction "C_C") (pintype "passive"))
      (node (ref "D039") (pin "A") (pinfunction "A_A") (pintype "passive"))
      (node (ref "D051") (pin "A") (pinfunction "A_A") (pintype "passive"))
      (node (ref "D102") (pin "A") (pinfunction "A_A") (pintype "passive"))
      (node (ref "D112") (pin "A") (pinfunction "A_A") (pintype "passive"))
      (node (ref "D121") (pin "A") (pinfunction "A_A") (pintype "passive"))
      (node (ref "D129") (pin "A") (pinfunction "A_A") (pintype "passive"))
      (node (ref "D136") (pin "A") (pinfunction "A_A") (pintype "passive"))
      (node (ref "D142") (pin "A") (pinfunction "A_A") (pintype "passive"))
      (node (ref "D147") (pin "A") (pinfunction "A_A") (pintype "passive"))
      (node (ref "D151") (pin "A") (pinfunction "A_A") (pintype "passive"))
      (node (ref "D154") (pin "A") (pinfunction "A_A") (pintype "passive"))
      (node (ref "J405") (pin "6") (pinfunction "6_6") (pintype "passive"))
      (node (ref "R4") (pin "7") (pinfunction "2_7") (pintype "passive"))
    )
    (net (code "39") (name "/Q15") (class "Default")
      (node (ref "D013") (pin "A") (pinfunction "A_A") (pintype "passive"))
      (node (ref "D014") (pin "C") (pinfunction "C_C") (pintype "passive"))
      (node (ref "D027") (pin "A") (pinfunction "A_A") (pintype "passive"))
      (node (ref "D040") (pin "A") (pinfunction "A_A") (pintype "passive"))
      (node (ref "D052") (pin "A") (pinfunction "A_A") (pintype "passive"))
      (node (ref "D103") (pin "A") (pinfunction "A_A") (pintype "passive"))
      (node (ref "D113") (pin "A") (pinfunction "A_A") (pintype "passive"))
      (node (ref "D122") (pin "A") (pinfunction "A_A") (pintype "passive"))
      (node (ref "D130") (pin "A") (pinfunction "A_A") (pintype "passive"))
      (node (ref "D137") (pin "A") (pinfunction "A_A") (pintype "passive"))
      (node (ref "D143") (pin "A") (pinfunction "A_A") (pintype "passive"))
      (node (ref "D148") (pin "A") (pinfunction "A_A") (pintype "passive"))
      (node (ref "D152") (pin "A") (pinfunction "A_A") (pintype "passive"))
      (node (ref "D155") (pin "A") (pinfunction "A_A") (pintype "passive"))
      (node (ref "D157") (pin "A") (pinfunction "A_A") (pintype "passive"))
      (node (ref "J405") (pin "7") (pinfunction "7_7") (pintype "passive"))
      (node (ref "R4") (pin "6") (pinfunction "2_6") (pintype "passive"))
    )
    (net (code "40") (name "/Q16") (class "Default")
      (node (ref "D014") (pin "A") (pinfunction "A_A") (pintype "passive"))
      (node (ref "D028") (pin "A") (pinfunction "A_A") (pintype "passive"))
      (node (ref "D041") (pin "A") (pinfunction "A_A") (pintype "passive"))
      (node (ref "D053") (pin "A") (pinfunction "A_A") (pintype "passive"))
      (node (ref "D104") (pin "A") (pinfunction "A_A") (pintype "passive"))
      (node (ref "D114") (pin "A") (pinfunction "A_A") (pintype "passive"))
      (node (ref "D123") (pin "A") (pinfunction "A_A") (pintype "passive"))
      (node (ref "D131") (pin "A") (pinfunction "A_A") (pintype "passive"))
      (node (ref "D138") (pin "A") (pinfunction "A_A") (pintype "passive"))
      (node (ref "D144") (pin "A") (pinfunction "A_A") (pintype "passive"))
      (node (ref "D149") (pin "A") (pinfunction "A_A") (pintype "passive"))
      (node (ref "D153") (pin "A") (pinfunction "A_A") (pintype "passive"))
      (node (ref "D156") (pin "A") (pinfunction "A_A") (pintype "passive"))
      (node (ref "D158") (pin "A") (pinfunction "A_A") (pintype "passive"))
      (node (ref "D159") (pin "A") (pinfunction "A_A") (pintype "passive"))
      (node (ref "J405") (pin "8") (pinfunction "8_8") (pintype "passive"))
      (node (ref "R4") (pin "5") (pinfunction "2_5") (pintype "passive"))
    )
    (net (code "41") (name "/RESET") (class "Default")
      (node (ref "C502") (pin "1") (pinfunction "1_1") (pintype "passive"))
      (node (ref "J003") (pin "1") (pinfunction "1_1") (pintype "passive"))
      (node (ref "J005") (pin "1") (pinfunction "1_1") (pintype "passive"))
      (node (ref "R606") (pin "5") (pinfunction "2_5") (pintype "passive"))
      (node (ref "S429") (pin "P$2") (pinfunction "2_P$2") (pintype "bidirectional"))
      (node (ref "U401") (pin "29") (pinfunction "PC6(/RESET)_29") (pintype "bidirectional"))
    )
    (net (code "42") (name "/USBD+") (class "Default")
      (node (ref "J001") (pin "1") (pinfunction "1_1") (pintype "passive"))
      (node (ref "J002") (pin "1") (pinfunction "1_1") (pintype "passive"))
      (node (ref "U501") (pin "15") (pinfunction "USBDP_15") (pintype "bidirectional"))
    )
    (net (code "43") (name "/USBD-") (class "Default")
      (node (ref "J001") (pin "2") (pinfunction "2_2") (pintype "passive"))
      (node (ref "J002") (pin "2") (pinfunction "2_2") (pintype "passive"))
      (node (ref "U501") (pin "16") (pinfunction "USBDM_16") (pintype "bidirectional"))
    )
    (net (code "44") (name "/USB_RX") (class "Default")
      (node (ref "U501") (pin "5") (pinfunction "RXD_5") (pintype "input"))
      (node (ref "U601") (pin "4") (pinfunction "OUT_4") (pintype "bidirectional"))
    )
    (net (code "45") (name "/USB_TX") (class "Default")
      (node (ref "U501") (pin "1") (pinfunction "TXD_1") (pintype "output"))
      (node (ref "U602") (pin "1") (pinfunction "I1_1") (pintype "bidirectional"))
      (node (ref "U603") (pin "1") (pinfunction "I1_1") (pintype "bidirectional"))
    )
    (net (code "46") (name "/XTAL1") (class "Default")
      (node (ref "C407") (pin "2") (pinfunction "2_2") (pintype "passive"))
      (node (ref "U401") (pin "7") (pinfunction "PB6(XTAL1/TOSC1)_7") (pintype "bidirectional"))
      (node (ref "Y401") (pin "1") (pinfunction "1_1") (pintype "passive"))
    )
    (net (code "47") (name "/XTAL2") (class "Default")
      (node (ref "C408") (pin "2") (pinfunction "2_2") (pintype "passive"))
      (node (ref "U401") (pin "8") (pinfunction "PB7(XTAL2/TOSC2)_8") (pintype "bidirectional"))
      (node (ref "Y401") (pin "3") (pinfunction "2_3") (pintype "passive"))
    )
    (net (code "48") (name "GND") (class "Default")
      (node (ref "C010") (pin "2") (pinfunction "2_2") (pintype "passive"))
      (node (ref "C407") (pin "1") (pinfunction "1_1") (pintype "passive"))
      (node (ref "C408") (pin "1") (pinfunction "1_1") (pintype "passive"))
      (node (ref "C418") (pin "1") (pinfunction "1_1") (pintype "passive"))
      (node (ref "C420") (pin "2") (pinfunction "2_2") (pintype "passive"))
      (node (ref "J001") (pin "4") (pinfunction "4_4") (pintype "passive"))
      (node (ref "J002") (pin "4") (pinfunction "4_4") (pintype "passive"))
      (node (ref "J003") (pin "3") (pinfunction "3_3") (pintype "passive"))
      (node (ref "J005") (pin "3") (pinfunction "3_3") (pintype "passive"))
      (node (ref "J402") (pin "1") (pinfunction "GND1_1") (pintype "bidirectional"))
      (node (ref "J402") (pin "5") (pinfunction "GND2_5") (pintype "bidirectional"))
      (node (ref "J403") (pin "1") (pinfunction "1_1") (pintype "passive"))
      (node (ref "J403") (pin "5") (pinfunction "5_5") (pintype "passive"))
      (node (ref "J404") (pin "1") (pinfunction "GND1_1") (pintype "bidirectional"))
      (node (ref "J404") (pin "5") (pinfunction "GND2_5") (pintype "bidirectional"))
      (node (ref "S429") (pin "P$1") (pinfunction "1_P$1") (pintype "bidirectional"))
      (node (ref "S429") (pin "P$3") (pinfunction "1_P$3") (pintype "bidirectional"))
      (node (ref "U401") (pin "21") (pinfunction "GND_21") (pintype "bidirectional"))
      (node (ref "U401") (pin "3") (pinfunction "GND_3") (pintype "bidirectional"))
      (node (ref "U401") (pin "5") (pinfunction "AGND_5") (pintype "bidirectional"))
      (node (ref "U501") (pin "18") (pinfunction "GND18_18") (pintype "power_in"))
      (node (ref "U501") (pin "21") (pinfunction "GND21_21") (pintype "power_in"))
      (node (ref "U501") (pin "25") (pinfunction "AGND_25") (pintype "power_in"))
      (node (ref "U501") (pin "7") (pinfunction "GND7_7") (pintype "power_in"))
      (node (ref "U601") (pin "2") (pinfunction "GND_2") (pintype "bidirectional"))
      (node (ref "U602") (pin "2") (pinfunction "GND_2") (pintype "bidirectional"))
      (node (ref "U603") (pin "2") (pinfunction "GND_2") (pintype "bidirectional"))
      (node (ref "Y401") (pin "2") (pinfunction "1_2") (pintype "bidirectional"))
      (node (ref "Y401") (pin "4") (pinfunction "1_4") (pintype "bidirectional"))
    )
    (net (code "49") (name "Net-(D501-PadC)") (class "Default")
      (node (ref "D501") (pin "C") (pinfunction "C_C") (pintype "passive"))
      (node (ref "R501") (pin "2") (pinfunction "2_2") (pintype "passive"))
    )
    (net (code "50") (name "Net-(D502-PadC)") (class "Default")
      (node (ref "D502") (pin "C") (pinfunction "C_C") (pintype "passive"))
      (node (ref "R502") (pin "2") (pinfunction "2_2") (pintype "passive"))
    )
    (net (code "51") (name "Net-(U401-AREF)") (class "Default")
      (node (ref "C420") (pin "1") (pinfunction "1_1") (pintype "passive"))
      (node (ref "U401") (pin "20") (pinfunction "AREF_20") (pintype "bidirectional"))
    )
    (net (code "52") (name "Net-(U501-DTR)") (class "Default")
      (node (ref "C502") (pin "2") (pinfunction "2_2") (pintype "passive"))
      (node (ref "U501") (pin "2") (pinfunction "DTR_2") (pintype "output"))
    )
    (net (code "53") (name "Net-(U501-RXLED)") (class "Default")
      (node (ref "R502") (pin "1") (pinfunction "1_1") (pintype "passive"))
      (node (ref "U501") (pin "22") (pinfunction "RXLED_22") (pintype "input"))
    )
    (net (code "54") (name "Net-(U501-TXLED)") (class "Default")
      (node (ref "R501") (pin "1") (pinfunction "1_1") (pintype "passive"))
      (node (ref "U501") (pin "23") (pinfunction "TXLED_23") (pintype "input"))
    )
    (net (code "55") (name "VCC") (class "Default")
      (node (ref "C010") (pin "1") (pinfunction "1_1") (pintype "passive"))
      (node (ref "C418") (pin "2") (pinfunction "2_2") (pintype "passive"))
      (node (ref "D501") (pin "A") (pinfunction "A_A") (pintype "passive"))
      (node (ref "D502") (pin "A") (pinfunction "A_A") (pintype "passive"))
      (node (ref "J001") (pin "3") (pinfunction "3_3") (pintype "passive"))
      (node (ref "J002") (pin "3") (pinfunction "3_3") (pintype "passive"))
      (node (ref "J003") (pin "2") (pinfunction "2_2") (pintype "passive"))
      (node (ref "J005") (pin "2") (pinfunction "2_2") (pintype "passive"))
      (node (ref "J402") (pin "2") (pinfunction "VCC_2") (pintype "bidirectional"))
      (node (ref "J403") (pin "2") (pinfunction "2_2") (pintype "passive"))
      (node (ref "J404") (pin "2") (pinfunction "VCC_2") (pintype "bidirectional"))
      (node (ref "R606") (pin "1") (pinfunction "1_1") (pintype "passive"))
      (node (ref "R606") (pin "2") (pinfunction "1_2") (pintype "passive"))
      (node (ref "R606") (pin "3") (pinfunction "1_3") (pintype "passive"))
      (node (ref "R606") (pin "4") (pinfunction "1_4") (pintype "passive"))
      (node (ref "U401") (pin "18") (pinfunction "AVCC_18") (pintype "bidirectional"))
      (node (ref "U401") (pin "4") (pinfunction "VCC_4") (pintype "bidirectional"))
      (node (ref "U401") (pin "6") (pinfunction "VCC_6") (pintype "bidirectional"))
      (node (ref "U501") (pin "20") (pinfunction "VCC_20") (pintype "power_in"))
      (node (ref "U501") (pin "4") (pinfunction "VCCIO_4") (pintype "power_in"))
      (node (ref "U601") (pin "5") (pinfunction "VCC_5") (pintype "bidirectional"))
      (node (ref "U602") (pin "5") (pinfunction "VCC_5") (pintype "bidirectional"))
      (node (ref "U603") (pin "5") (pinfunction "VCC_5") (pintype "bidirectional"))
    )
    (net (code "56") (name "unconnected-(U501-3V3OUT-Pad17)") (class "Default")
      (node (ref "U501") (pin "17") (pinfunction "3V3OUT_17") (pintype "output"))
    )
    (net (code "57") (name "unconnected-(U501-CTS-Pad11)") (class "Default")
      (node (ref "U501") (pin "11") (pinfunction "CTS_11") (pintype "input"))
    )
    (net (code "58") (name "unconnected-(U501-DCD-Pad10)") (class "Default")
      (node (ref "U501") (pin "10") (pinfunction "DCD_10") (pintype "input"))
    )
    (net (code "59") (name "unconnected-(U501-DSR-Pad9)") (class "Default")
      (node (ref "U501") (pin "9") (pinfunction "DSR_9") (pintype "input"))
    )
    (net (code "60") (name "unconnected-(U501-OSCI-Pad27)") (class "Default")
      (node (ref "U501") (pin "27") (pinfunction "OSCI_27") (pintype "input"))
    )
    (net (code "61") (name "unconnected-(U501-OSCO-Pad28)") (class "Default")
      (node (ref "U501") (pin "28") (pinfunction "OSCO_28") (pintype "output"))
    )
    (net (code "62") (name "unconnected-(U501-PWREN-Pad14)") (class "Default")
      (node (ref "U501") (pin "14") (pinfunction "PWREN_14") (pintype "input"))
    )
    (net (code "63") (name "unconnected-(U501-RESET-Pad19)") (class "Default")
      (node (ref "U501") (pin "19") (pinfunction "RESET_19") (pintype "input"))
    )
    (net (code "64") (name "unconnected-(U501-RI-Pad6)") (class "Default")
      (node (ref "U501") (pin "6") (pinfunction "RI_6") (pintype "input"))
    )
    (net (code "65") (name "unconnected-(U501-RTS-Pad3)") (class "Default")
      (node (ref "U501") (pin "3") (pinfunction "RTS_3") (pintype "output"))
    )
    (net (code "66") (name "unconnected-(U501-SLEEP-Pad12)") (class "Default")
      (node (ref "U501") (pin "12") (pinfunction "SLEEP_12") (pintype "input"))
    )
    (net (code "67") (name "unconnected-(U501-TEST-Pad26)") (class "Default")
      (node (ref "U501") (pin "26") (pinfunction "TEST_26") (pintype "input"))
    )
    (net (code "68") (name "unconnected-(U501-TXDEN-Pad13)") (class "Default")
      (node (ref "U501") (pin "13") (pinfunction "TXDEN_13") (pintype "input"))
    )
  )
)
